# Interface_-_CAN.net
KiCad netlist of a schematic drawn in Altium Designer
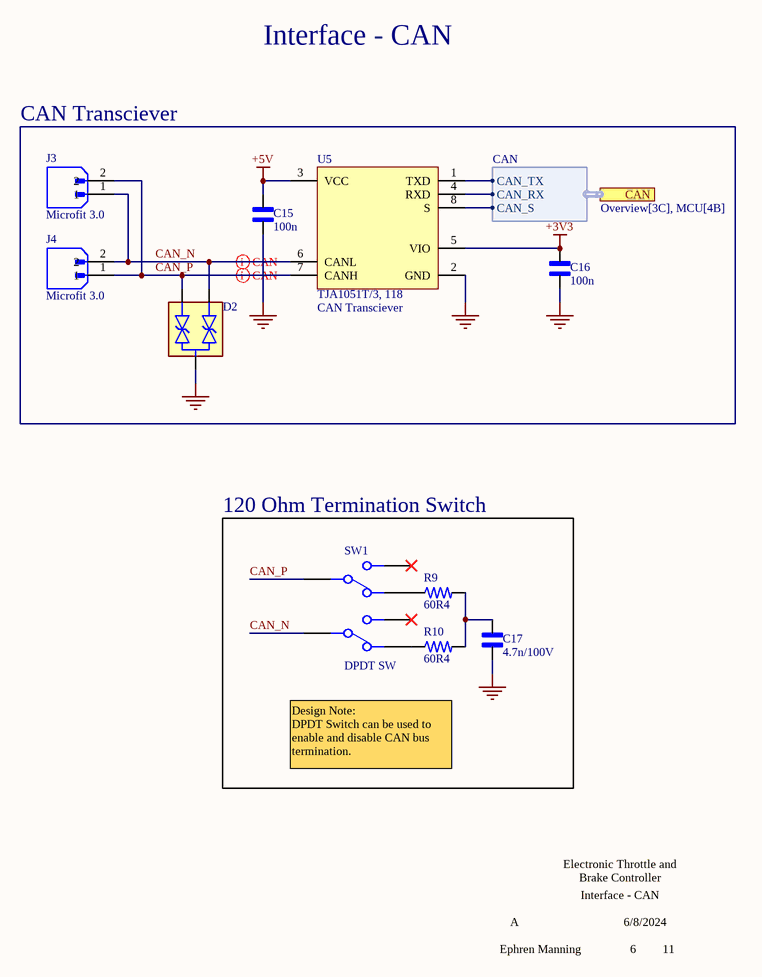
[diagram p0: Interface - CAN.SchDoc]

(export (version "E")
  (design (tool "Eeschema 10.0.6"))
  (components
    (comp (ref "C15")
      (value "100n")
      (footprint "CAP_0402-Footprint-1")
      (description "100nF 10V 10% 0402 CAP")
      (fields (field (name "DIGIKEY PART NUMBER") "1276-1002-1-ND"))
      (libsource (lib "SAE @ UIC Formula Electric") (part "CAP_0402-Symbol-1"))
    )
    (comp (ref "C16")
      (value "100n")
      (footprint "CAP_0402-Footprint-1")
      (description "100nF 10V 10% 0402 CAP")
      (fields (field (name "DIGIKEY PART NUMBER") "1276-1002-1-ND"))
      (libsource (lib "SAE @ UIC Formula Electric") (part "CAP_0402-Symbol-1"))
    )
    (comp (ref "C17")
      (value "4.7n/100V")
      (footprint "CAP_0402-Footprint-1")
      (description "4.7nF 100V 10% 0402 Ceramic Capacitor")
      (fields (field (name "DIGIKEY PART NUMBER") "490-4765-1-ND"))
      (libsource (lib "SAE @ UIC Formula Electric") (part "CAP_0402-Symbol-1"))
    )
    (comp (ref "D2")
      (value "ESD2CANFD24DBZRQ1")
      (footprint "SOT95P237X112-3N")
      (description "Dual TVS Protection Diodes")
      (fields (field (name "DIGIKEY PART NUMBER") "296-ESD2CANFD24DBZRQ1CT-ND"))
      (libsource (lib "SAE @ UIC Formula Electric") (part "ESD2CANFD24DBZRQ1"))
    )
    (comp (ref "J3")
      (value "Microfit 3.0")
      (footprint "MOLEX_436500216")
      (description "1x2 Gold Microfit")
      (fields (field (name "DIGIKEY PART NUMBER") "WM1922-ND"))
      (libsource (lib "SAE @ UIC Formula Electric") (part "436500216"))
    )
    (comp (ref "J4")
      (value "Microfit 3.0")
      (footprint "MOLEX_436500216")
      (description "1x2 Gold Microfit")
      (fields (field (name "DIGIKEY PART NUMBER") "WM1922-ND"))
      (libsource (lib "SAE @ UIC Formula Electric") (part "436500216"))
    )
    (comp (ref "R9")
      (value "60R4")
      (footprint "RES_0402-Footprint-1")
      (description "60.4 Ohm 1% 1/16W 0402 Resistor")
      (fields (field (name "DIGIKEY PART NUMBER") "311-60.4LRCT-ND"))
      (libsource (lib "SAE @ UIC Formula Electric") (part "RES_0402_Symbol"))
    )
    (comp (ref "R10")
      (value "60R4")
      (footprint "RES_0402-Footprint-1")
      (description "60.4 Ohm 1% 1/16W 0402 Resistor")
      (fields (field (name "DIGIKEY PART NUMBER") "311-60.4LRCT-ND"))
      (libsource (lib "SAE @ UIC Formula Electric") (part "RES_0402_Symbol"))
    )
    (comp (ref "SW1")
      (value "DPDT SW")
      (footprint "SW_JS202011JCQN")
      (description "DPDT SMD SWITCH 6V 300MA")
      (fields (field (name "DIGIKEY PART NUMBER") "CKN10723CT-ND"))
      (libsource (lib "SAE @ UIC Formula Electric") (part "JS202011JCQN"))
    )
    (comp (ref "U5")
      (value "TJA1051T/3, 118")
      (footprint "SOIC127P600X175-8N")
      (description "CAN Transceiver, NXP")
      (fields (field (name "DIGIKEY PART NUMBER") "568-8684-1-ND"))
      (libsource (lib "SAE @ UIC Formula Electric") (part "TJA1051T_3, 118-Symbol-1"))
    )
  )
  (nets
    (net (code "2") (name "+3V3") (class "Default")
      (node (ref "C16") (pin "2") (pinfunction "2_2") (pintype "passive"))
      (node (ref "U5") (pin "5") (pinfunction "VIO_5") (pintype "passive"))
    )
    (net (code "3") (name "+5V") (class "Default")
      (node (ref "C15") (pin "2") (pinfunction "2_2") (pintype "passive"))
      (node (ref "U5") (pin "3") (pinfunction "VCC_3") (pintype "passive"))
    )
    (net (code "4") (name "/CAN_N") (class "Default")
      (node (ref "D2") (pin "1") (pinfunction "IO1_1") (pintype "passive"))
      (node (ref "J3") (pin "1") (pinfunction "1_1") (pintype "passive"))
      (node (ref "J4") (pin "2") (pinfunction "2_2") (pintype "passive"))
      (node (ref "SW1") (pin "6") (pinfunction "6_6") (pintype "passive"))
      (node (ref "U5") (pin "6") (pinfunction "CANL_6") (pintype "passive"))
    )
    (net (code "5") (name "/CAN_P") (class "Default")
      (node (ref "D2") (pin "2") (pinfunction "IO2_2") (pintype "passive"))
      (node (ref "J3") (pin "2") (pinfunction "2_2") (pintype "passive"))
      (node (ref "J4") (pin "1") (pinfunction "1_1") (pintype "passive"))
      (node (ref "SW1") (pin "2") (pinfunction "2_2") (pintype "passive"))
      (node (ref "U5") (pin "7") (pinfunction "CANH_7") (pintype "passive"))
    )
    (net (code "6") (name "/CAN_RX") (class "Default")
      (node (ref "U5") (pin "4") (pinfunction "RXD_4") (pintype "passive"))
    )
    (net (code "7") (name "/CAN_S") (class "Default")
      (node (ref "U5") (pin "8") (pinfunction "S_8") (pintype "passive"))
    )
    (net (code "8") (name "/CAN_TX") (class "Default")
      (node (ref "U5") (pin "1") (pinfunction "TXD_1") (pintype "passive"))
    )
    (net (code "10") (name "GND") (class "Default")
      (node (ref "C15") (pin "1") (pinfunction "1_1") (pintype "passive"))
      (node (ref "C16") (pin "1") (pinfunction "1_1") (pintype "passive"))
      (node (ref "C17") (pin "1") (pinfunction "1_1") (pintype "passive"))
      (node (ref "D2") (pin "3") (pinfunction "GND_3") (pintype "power_in"))
      (node (ref "U5") (pin "2") (pinfunction "GND_2") (pintype "passive"))
    )
    (net (code "11") (name "Net-(C17-Pad2)") (class "Default")
      (node (ref "C17") (pin "2") (pinfunction "2_2") (pintype "passive"))
      (node (ref "R10") (pin "2") (pinfunction "2_2") (pintype "passive"))
      (node (ref "R9") (pin "2") (pinfunction "2_2") (pintype "passive"))
    )
    (net (code "12") (name "Net-(R9-Pad1)") (class "Default")
      (node (ref "R9") (pin "1") (pinfunction "1_1") (pintype "passive"))
      (node (ref "SW1") (pin "3") (pinfunction "3_3") (pintype "passive"))
    )
    (net (code "13") (name "Net-(R10-Pad1)") (class "Default")
      (node (ref "R10") (pin "1") (pinfunction "1_1") (pintype "passive"))
      (node (ref "SW1") (pin "7") (pinfunction "7_7") (pintype "passive"))
    )
    (net (code "14") (name "unconnected-(SW1-Pad1)") (class "Default")
      (node (ref "SW1") (pin "1") (pinfunction "1_1") (pintype "passive+no_connect"))
    )
    (net (code "15") (name "unconnected-(SW1-Pad5)") (class "Default")
      (node (ref "SW1") (pin "5") (pinfunction "5_5") (pintype "passive+no_connect"))
    )
  )
)
